# DE-120824.net
KiCad netlist of a schematic drawn in Altium Designer
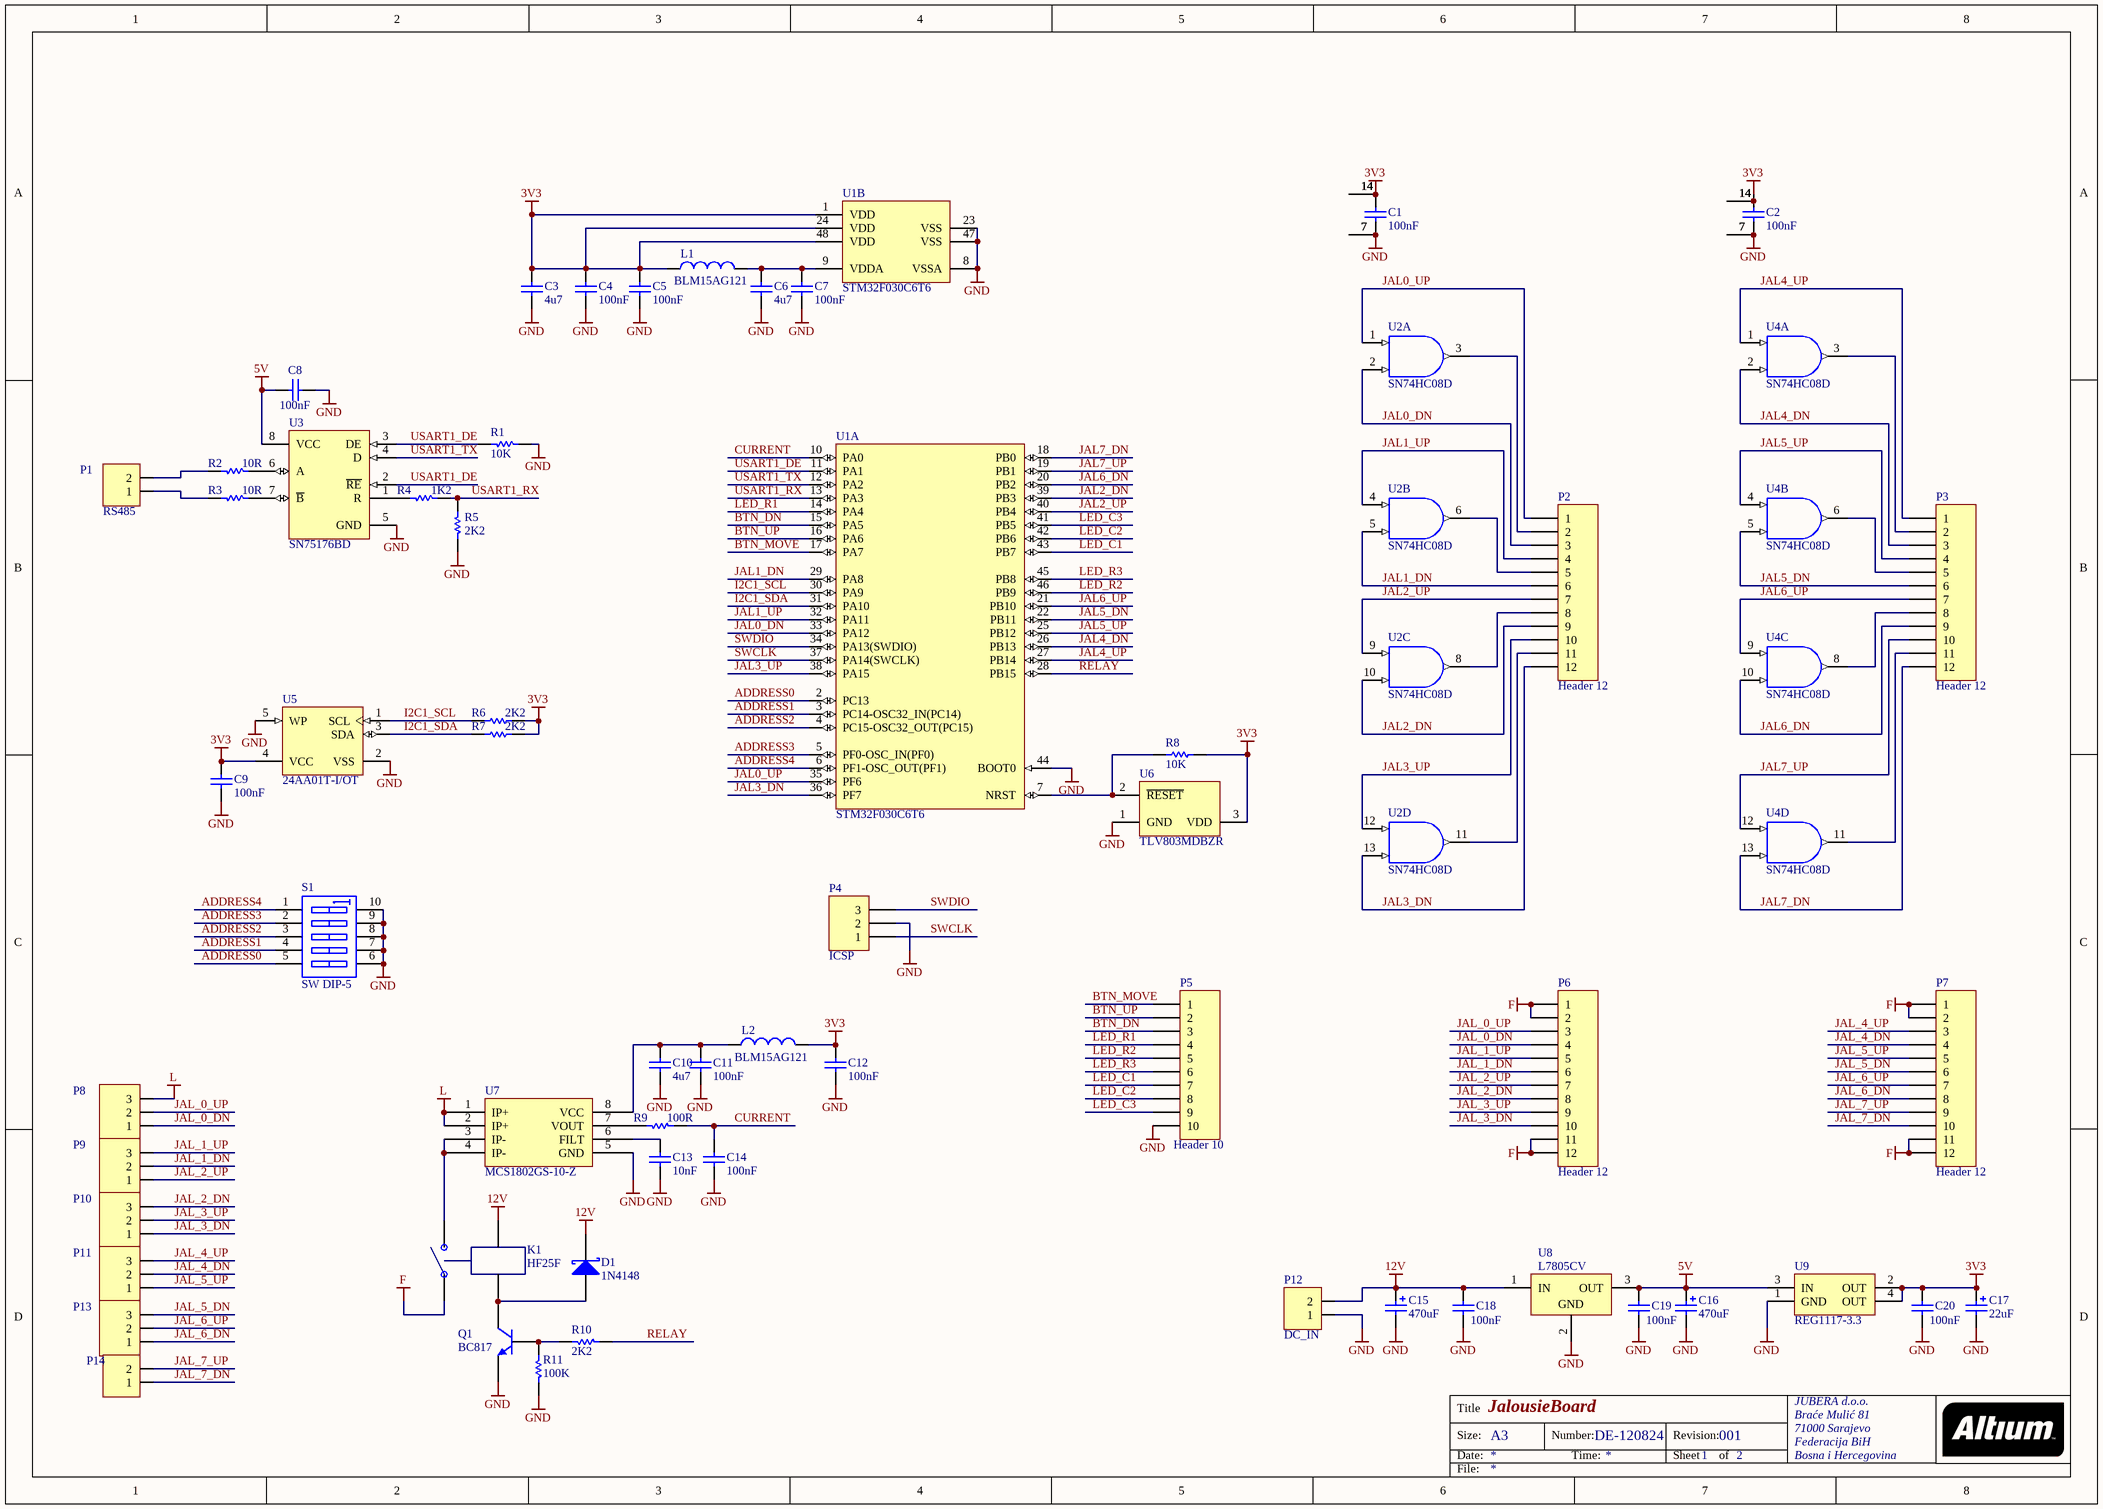
[diagram p0: DE-120824.SchDoc]

(export (version "E")
  (design (tool "Eeschema 10.0.6"))
  (components
    (comp (ref "C1")
      (value "100nF")
      (footprint "0603")
      (description "Ceramic Chip Capacitor - Standard")
      (fields (field (name "Comment") "C0603") (field (name "PUBLISHER") "Altium Limited"))
      (libsource (lib "DE-120824") (part "C0603"))
    )
    (comp (ref "C2")
      (value "100nF")
      (footprint "0603")
      (description "Ceramic Chip Capacitor - Standard")
      (fields (field (name "Comment") "C0603") (field (name "PUBLISHER") "Altium Limited"))
      (libsource (lib "DE-120824") (part "C0603"))
    )
    (comp (ref "C3")
      (value "4u7")
      (footprint "0805")
      (description "Ceramic Chip Capacitor - Standard")
      (fields (field (name "Comment") "C0805") (field (name "PUBLISHER") "Altium Limited"))
      (libsource (lib "DE-120824") (part "C0805"))
    )
    (comp (ref "C4")
      (value "100nF")
      (footprint "0603")
      (description "Ceramic Chip Capacitor - Standard")
      (fields (field (name "Comment") "C0603") (field (name "PUBLISHER") "Altium Limited"))
      (libsource (lib "DE-120824") (part "C0603"))
    )
    (comp (ref "C5")
      (value "100nF")
      (footprint "0603")
      (description "Ceramic Chip Capacitor - Standard")
      (fields (field (name "Comment") "C0603") (field (name "PUBLISHER") "Altium Limited"))
      (libsource (lib "DE-120824") (part "C0603"))
    )
    (comp (ref "C6")
      (value "4u7")
      (footprint "0805")
      (description "Ceramic Chip Capacitor - Standard")
      (fields (field (name "Comment") "C0805") (field (name "PUBLISHER") "Altium Limited"))
      (libsource (lib "DE-120824") (part "C0805"))
    )
    (comp (ref "C7")
      (value "100nF")
      (footprint "0603")
      (description "Ceramic Chip Capacitor - Standard")
      (fields (field (name "Comment") "C0603") (field (name "PUBLISHER") "Altium Limited"))
      (libsource (lib "DE-120824") (part "C0603"))
    )
    (comp (ref "C8")
      (value "100nF")
      (footprint "0603")
      (description "Ceramic Chip Capacitor - Standard")
      (fields (field (name "PUBLISHER") "Altium Limited"))
      (libsource (lib "DE-220817") (part "C0603"))
    )
    (comp (ref "C9")
      (value "100nF")
      (footprint "0603")
      (description "Ceramic Chip Capacitor - Standard")
      (fields (field (name "Comment") "C0603") (field (name "PUBLISHER") "Altium Limited"))
      (libsource (lib "DE-120824") (part "C0603"))
    )
    (comp (ref "C10")
      (value "4u7")
      (footprint "0805")
      (description "Ceramic Chip Capacitor - Standard")
      (fields (field (name "Comment") "C0805") (field (name "PUBLISHER") "Altium Limited"))
      (libsource (lib "DE-120824") (part "C0805"))
    )
    (comp (ref "C11")
      (value "100nF")
      (footprint "0603")
      (description "Ceramic Chip Capacitor - Standard")
      (fields (field (name "Comment") "C0603") (field (name "PUBLISHER") "Altium Limited"))
      (libsource (lib "DE-120824") (part "C0603"))
    )
    (comp (ref "C12")
      (value "100nF")
      (footprint "0603")
      (description "Ceramic Chip Capacitor - Standard")
      (fields (field (name "Comment") "C0603") (field (name "PUBLISHER") "Altium Limited"))
      (libsource (lib "DE-120824") (part "C0603"))
    )
    (comp (ref "C13")
      (value "10nF")
      (footprint "0603")
      (description "Ceramic Chip Capacitor - Standard")
      (fields (field (name "Comment") "C0603") (field (name "PUBLISHER") "Altium Limited"))
      (libsource (lib "DE-120824") (part "C0603"))
    )
    (comp (ref "C14")
      (value "100nF")
      (footprint "0603")
      (description "Ceramic Chip Capacitor - Standard")
      (fields (field (name "Comment") "C0603") (field (name "PUBLISHER") "Altium Limited"))
      (libsource (lib "DE-120824") (part "C0603"))
    )
    (comp (ref "C15")
      (value "470uF")
      (footprint "CAPPR5-10X12.5")
      (description "Aluminum Electrolytic Capacitor, Radial Style with Long Leads: 470uF, 25V")
      (fields (field (name "PUBLISHER") "Altium Limited"))
      (libsource (lib "DE-010824") (part "EKA00DC347E00"))
    )
    (comp (ref "C16")
      (value "470uF")
      (footprint "CAPPR5-10X12.5")
      (description "Aluminum Electrolytic Capacitor, Radial Style with Long Leads: 470uF, 25V")
      (fields (field (name "PUBLISHER") "Altium Limited"))
      (libsource (lib "DE-010824") (part "EKA00DC347E00"))
    )
    (comp (ref "C17")
      (value "22uF")
      (footprint "CAPPR2-5X11")
      (description "Aluminum Electrolytic Capacitor, Radial Style with Long Leads: 47uF, 35V")
      (fields (field (name "PUBLISHER") "Altium Limited"))
      (libsource (lib "DE-010824") (part "EKA00AA247F00"))
    )
    (comp (ref "C18")
      (value "100nF")
      (footprint "0603")
      (description "Ceramic Chip Capacitor - Standard")
      (fields (field (name "PUBLISHER") "Altium Limited"))
      (libsource (lib "DE-220817") (part "C0603"))
    )
    (comp (ref "C19")
      (value "100nF")
      (footprint "0603")
      (description "Ceramic Chip Capacitor - Standard")
      (fields (field (name "PUBLISHER") "Altium Limited"))
      (libsource (lib "DE-220817") (part "C0603"))
    )
    (comp (ref "C20")
      (value "100nF")
      (footprint "0603")
      (description "Ceramic Chip Capacitor - Standard")
      (fields (field (name "PUBLISHER") "Altium Limited"))
      (libsource (lib "DE-220817") (part "C0603"))
    )
    (comp (ref "D1")
      (value "1N4148")
      (footprint "SOD323")
      (description "Schottky Barrier Diode")
      (fields (field (name "PUBLISHER") "Altium Limited"))
      (libsource (lib "DE-120824") (part "1PS76SB10"))
    )
    (comp (ref "K1")
      (value "HF25F")
      (footprint "HF25F")
      (description "PCB relay 250VAC/20A 30VDC/16A")
      (libsource (lib "DE-120824") (part "HF25F"))
    )
    (comp (ref "L1")
      (value "BLM15AG121")
      (footprint "0402-A")
      (description "SMD chip inductor")
      (fields (field (name "PUBLISHER") "Altium Limited"))
      (libsource (lib "DE-120824") (part "Chip inductor"))
    )
    (comp (ref "L2")
      (value "BLM15AG121")
      (footprint "0402-A")
      (description "SMD chip inductor")
      (fields (field (name "PUBLISHER") "Altium Limited"))
      (libsource (lib "DE-120824") (part "Chip inductor"))
    )
    (comp (ref "P1")
      (value "RS485")
      (footprint "TERMINAL BLOK 2")
      (description "Terminal blok konektor 3,5 mm")
      (libsource (lib "DE-120824") (part "TERMINAL BLOK 2"))
    )
    (comp (ref "P2")
      (value "Header 12")
      (footprint "HDR1X12")
      (description "Header, 12-Pin")
      (fields (field (name "PUBLISHER") "Altium Limited"))
      (libsource (lib "Miscellaneous Connectors") (part "Header 12"))
    )
    (comp (ref "P3")
      (value "Header 12")
      (footprint "HDR1X12")
      (description "Header, 12-Pin")
      (fields (field (name "PUBLISHER") "Altium Limited"))
      (libsource (lib "Miscellaneous Connectors") (part "Header 12"))
    )
    (comp (ref "P4")
      (value "ICSP")
      (footprint "HDR1X3")
      (description "Header, 3-Pin")
      (fields (field (name "PUBLISHER") "Altium Limited"))
      (libsource (lib "Miscellaneous Connectors") (part "Header 3"))
    )
    (comp (ref "P5")
      (value "Header 10")
      (footprint "HDR1X10")
      (description "Header, 10-Pin")
      (fields (field (name "PUBLISHER") "Altium Limited"))
      (libsource (lib "Miscellaneous Connectors") (part "Header 10"))
    )
    (comp (ref "P6")
      (value "Header 12")
      (footprint "HDR1X12")
      (description "Header, 12-Pin")
      (fields (field (name "PUBLISHER") "Altium Limited"))
      (libsource (lib "Miscellaneous Connectors") (part "Header 12"))
    )
    (comp (ref "P7")
      (value "Header 12")
      (footprint "HDR1X12")
      (description "Header, 12-Pin")
      (fields (field (name "PUBLISHER") "Altium Limited"))
      (libsource (lib "Miscellaneous Connectors") (part "Header 12"))
    )
    (comp (ref "P8")
      (value "~")
      (footprint "TERMINAL BLOK 3")
      (description "3 pinski terminal blok konektor")
      (libsource (lib "DE-120824") (part "TERMINAL BLOK 3"))
    )
    (comp (ref "P9")
      (value "~")
      (footprint "TERMINAL BLOK 3")
      (description "3 pinski terminal blok konektor")
      (libsource (lib "DE-120824") (part "TERMINAL BLOK 3"))
    )
    (comp (ref "P10")
      (value "~")
      (footprint "TERMINAL BLOK 3")
      (description "3 pinski terminal blok konektor")
      (libsource (lib "DE-120824") (part "TERMINAL BLOK 3"))
    )
    (comp (ref "P11")
      (value "~")
      (footprint "TERMINAL BLOK 3")
      (description "3 pinski terminal blok konektor")
      (libsource (lib "DE-120824") (part "TERMINAL BLOK 3"))
    )
    (comp (ref "P12")
      (value "DC_IN")
      (footprint "TERMINAL BLOK 2")
      (description "Terminal blok konektor 3,5 mm")
      (libsource (lib "DE-010824") (part "TERMINAL BLOK 2"))
    )
    (comp (ref "P13")
      (value "~")
      (footprint "TERMINAL BLOK 3")
      (description "3 pinski terminal blok konektor")
      (libsource (lib "DE-120824") (part "TERMINAL BLOK 3"))
    )
    (comp (ref "P14")
      (value "~")
      (footprint "TERMINAL BLOK 2")
      (description "Terminal blok konektor 3,5 mm")
      (libsource (lib "DE-120824") (part "TERMINAL BLOK 2"))
    )
    (comp (ref "Q1")
      (value "BC817")
      (footprint "SOT23_N")
      (description "NPN General-purpose Transistor")
      (fields (field (name "PUBLISHER") "Altium Limited"))
      (libsource (lib "DE-120824") (part "BC817"))
    )
    (comp (ref "R1")
      (value "10K")
      (footprint "ERA-0603")
      (fields (field (name "PUBLISHER") "Altium Limited"))
      (libsource (lib "DE-220817") (part "ERAV"))
    )
    (comp (ref "R2")
      (value "10R")
      (footprint "ERA-0603")
      (fields (field (name "PUBLISHER") "Altium Limited"))
      (libsource (lib "DE-220817") (part "ERAV"))
    )
    (comp (ref "R3")
      (value "10R")
      (footprint "ERA-0603")
      (fields (field (name "PUBLISHER") "Altium Limited"))
      (libsource (lib "DE-220817") (part "ERAV"))
    )
    (comp (ref "R4")
      (value "1K2")
      (footprint "ERA-0603")
      (fields (field (name "PUBLISHER") "Altium Limited"))
      (libsource (lib "DE-220817") (part "ERAV"))
    )
    (comp (ref "R5")
      (value "2K2")
      (footprint "ERA-0603")
      (fields (field (name "PUBLISHER") "Altium Limited"))
      (libsource (lib "DE-220817") (part "ERAV"))
    )
    (comp (ref "R6")
      (value "2K2")
      (footprint "ERA-0603")
      (fields (field (name "PUBLISHER") "Altium Limited"))
      (libsource (lib "DE-120824") (part "ERA3Y"))
    )
    (comp (ref "R7")
      (value "2K2")
      (footprint "ERA-0603")
      (fields (field (name "PUBLISHER") "Altium Limited"))
      (libsource (lib "DE-120824") (part "ERA3Y"))
    )
    (comp (ref "R8")
      (value "10K")
      (footprint "ERA-0603")
      (fields (field (name "PUBLISHER") "Altium Limited"))
      (libsource (lib "DE-120824") (part "ERA3Y"))
    )
    (comp (ref "R9")
      (value "100R")
      (footprint "ERA-0603")
      (fields (field (name "PUBLISHER") "Altium Limited"))
      (libsource (lib "DE-220817") (part "ERAV"))
    )
    (comp (ref "R10")
      (value "2K2")
      (footprint "ERA-0603")
      (fields (field (name "PUBLISHER") "Altium Limited"))
      (libsource (lib "DE-220817") (part "ERAV"))
    )
    (comp (ref "R11")
      (value "100K")
      (footprint "ERA-0603")
      (fields (field (name "PUBLISHER") "Altium Limited"))
      (libsource (lib "DE-220817") (part "ERAV"))
    )
    (comp (ref "S1")
      (value "SW DIP-5")
      (footprint "N10A")
      (description "DIP Switch, 5 Position, SPST")
      (fields (field (name "PUBLISHER") "Altium Limited"))
      (libsource (lib "Miscellaneous Devices") (part "SW DIP-5"))
    )
    (comp (ref "U1")
      (value "STM32F030C6T6")
      (footprint "STM-LQFP48_N")
      (libsource (lib "STMicroelectronics STM32 F0") (part "STM32F030C6T6"))
    )
    (comp (ref "U2")
      (value "SN74HC08D")
      (footprint "D014_N")
      (description "Quadruple 2-Input Positive-AND Gate")
      (fields (field (name "PUBLISHER") "Altium Limited"))
      (libsource (lib "") (part "SN74HC08D_6"))
    )
    (comp (ref "U3")
      (value "SN75176BD")
      (footprint "D008_N")
      (description "Differential Bus Transceiver")
      (fields (field (name "PUBLISHER") "Altium Limited"))
      (libsource (lib "DE-010824") (part "SN75176BD"))
    )
    (comp (ref "U4")
      (value "SN74HC08D")
      (footprint "D014_N")
      (description "Quadruple 2-Input Positive-AND Gate")
      (fields (field (name "PUBLISHER") "Altium Limited"))
      (libsource (lib "") (part "SN74HC08D_4"))
    )
    (comp (ref "U5")
      (value "24AA01T-I/OT")
      (footprint "SOT-23-OT5_N")
      (description "1Kbit, 400kHz, 1.8V, I2C Serial EEPROM, 5-Pin SOT-23, Industrial Temperature, Tape and Reel")
      (fields (field (name "PUBLISHER") "Altium Limited"))
      (libsource (lib "Microchip Memory I2C Serial EEPROM") (part "24AA01T-I/OT"))
    )
    (comp (ref "U6")
      (value "TLV803MDBZR")
      (footprint "DBZ3_N")
      (fields (field (name "MANUFACTURER") "Texas Instruments"))
      (libsource (lib "TI Power Management Supervisor and Reset IC") (part "TLV803MDBZR"))
    )
    (comp (ref "U7")
      (value "MCS1802GS-10-Z")
      (footprint "SOIC-SN8_N")
      (libsource (lib "DE-120824") (part "ACS71240"))
    )
    (comp (ref "U8")
      (value "L7805CV")
      (footprint "TO220")
      (description "Positive Voltage Regulator, 5V, 3-Pin TO-220")
      (libsource (lib "DE-010824") (part "L7805CV"))
    )
    (comp (ref "U9")
      (value "REG1117-3.3")
      (footprint "ZZ311")
      (description "800mA and 1A Low Dropout Positive Regulator 2.85V, 3.3V, 5V, and Adjustable")
      (fields (field (name "PUBLISHER") "Altium Limited"))
      (libsource (lib "DE-010824") (part "REG1117-3.3"))
    )
  )
  (nets
    (net (code "1") (name "/ADDRESS0") (class "Default")
      (node (ref "S1") (pin "5") (pinfunction "A5_5") (pintype "passive"))
      (node (ref "U1") (pin "2") (pinfunction "PC13_2") (pintype "bidirectional"))
    )
    (net (code "2") (name "/ADDRESS1") (class "Default")
      (node (ref "S1") (pin "4") (pinfunction "A4_4") (pintype "passive"))
      (node (ref "U1") (pin "3") (pinfunction "PC14-OSC32_IN(PC14)_3") (pintype "bidirectional"))
    )
    (net (code "3") (name "/ADDRESS2") (class "Default")
      (node (ref "S1") (pin "3") (pinfunction "A3_3") (pintype "passive"))
      (node (ref "U1") (pin "4") (pinfunction "PC15-OSC32_OUT(PC15)_4") (pintype "bidirectional"))
    )
    (net (code "4") (name "/ADDRESS3") (class "Default")
      (node (ref "S1") (pin "2") (pinfunction "A2_2") (pintype "passive"))
      (node (ref "U1") (pin "5") (pinfunction "PF0-OSC_IN(PF0)_5") (pintype "bidirectional"))
    )
    (net (code "5") (name "/ADDRESS4") (class "Default")
      (node (ref "S1") (pin "1") (pinfunction "A1_1") (pintype "passive"))
      (node (ref "U1") (pin "6") (pinfunction "PF1-OSC_OUT(PF1)_6") (pintype "bidirectional"))
    )
    (net (code "6") (name "/BTN_DN") (class "Default")
      (node (ref "P5") (pin "3") (pinfunction "3_3") (pintype "passive"))
      (node (ref "U1") (pin "15") (pinfunction "PA5_15") (pintype "bidirectional"))
    )
    (net (code "7") (name "/BTN_MOVE") (class "Default")
      (node (ref "P5") (pin "1") (pinfunction "1_1") (pintype "passive"))
      (node (ref "U1") (pin "17") (pinfunction "PA7_17") (pintype "bidirectional"))
    )
    (net (code "8") (name "/BTN_UP") (class "Default")
      (node (ref "P5") (pin "2") (pinfunction "2_2") (pintype "passive"))
      (node (ref "U1") (pin "16") (pinfunction "PA6_16") (pintype "bidirectional"))
    )
    (net (code "9") (name "/CURRENT") (class "Default")
      (node (ref "C14") (pin "2") (pinfunction "2_2") (pintype "passive"))
      (node (ref "R9") (pin "1") (pinfunction "1_1") (pintype "passive"))
      (node (ref "U1") (pin "10") (pinfunction "PA0_10") (pintype "bidirectional"))
    )
    (net (code "10") (name "/I2C1_SCL") (class "Default")
      (node (ref "R6") (pin "1") (pinfunction "1_1") (pintype "passive"))
      (node (ref "U1") (pin "30") (pinfunction "PA9_30") (pintype "bidirectional"))
      (node (ref "U5") (pin "1") (pinfunction "SCL_1") (pintype "input"))
    )
    (net (code "11") (name "/I2C1_SDA") (class "Default")
      (node (ref "R7") (pin "1") (pinfunction "1_1") (pintype "passive"))
      (node (ref "U1") (pin "31") (pinfunction "PA10_31") (pintype "bidirectional"))
      (node (ref "U5") (pin "3") (pinfunction "SDA_3") (pintype "bidirectional"))
    )
    (net (code "12") (name "/JAL0_DN") (class "Default")
      (node (ref "P2") (pin "3") (pinfunction "3_3") (pintype "passive"))
      (node (ref "U1") (pin "33") (pinfunction "PA12_33") (pintype "bidirectional"))
      (node (ref "U2") (pin "2") (pinfunction "B_2") (pintype "input"))
    )
    (net (code "13") (name "/JAL0_UP") (class "Default")
      (node (ref "P2") (pin "1") (pinfunction "1_1") (pintype "passive"))
      (node (ref "U1") (pin "35") (pinfunction "PF6_35") (pintype "bidirectional"))
      (node (ref "U2") (pin "1") (pinfunction "A_1") (pintype "input"))
    )
    (net (code "14") (name "/JAL1_DN") (class "Default")
      (node (ref "P2") (pin "6") (pinfunction "6_6") (pintype "passive"))
      (node (ref "U1") (pin "29") (pinfunction "PA8_29") (pintype "bidirectional"))
      (node (ref "U2") (pin "5") (pinfunction "B_5") (pintype "input"))
    )
    (net (code "15") (name "/JAL1_UP") (class "Default")
      (node (ref "P2") (pin "4") (pinfunction "4_4") (pintype "passive"))
      (node (ref "U1") (pin "32") (pinfunction "PA11_32") (pintype "bidirectional"))
      (node (ref "U2") (pin "4") (pinfunction "A_4") (pintype "input"))
    )
    (net (code "16") (name "/JAL2_DN") (class "Default")
      (node (ref "P2") (pin "9") (pinfunction "9_9") (pintype "passive"))
      (node (ref "U1") (pin "39") (pinfunction "PB3_39") (pintype "bidirectional"))
      (node (ref "U2") (pin "10") (pinfunction "B_10") (pintype "input"))
    )
    (net (code "17") (name "/JAL2_UP") (class "Default")
      (node (ref "P2") (pin "7") (pinfunction "7_7") (pintype "passive"))
      (node (ref "U1") (pin "40") (pinfunction "PB4_40") (pintype "bidirectional"))
      (node (ref "U2") (pin "9") (pinfunction "A_9") (pintype "input"))
    )
    (net (code "18") (name "/JAL3_DN") (class "Default")
      (node (ref "P2") (pin "12") (pinfunction "12_12") (pintype "passive"))
      (node (ref "U1") (pin "36") (pinfunction "PF7_36") (pintype "bidirectional"))
      (node (ref "U2") (pin "13") (pinfunction "B_13") (pintype "input"))
    )
    (net (code "19") (name "/JAL3_UP") (class "Default")
      (node (ref "P2") (pin "10") (pinfunction "10_10") (pintype "passive"))
      (node (ref "U1") (pin "38") (pinfunction "PA15_38") (pintype "bidirectional"))
      (node (ref "U2") (pin "12") (pinfunction "A_12") (pintype "input"))
    )
    (net (code "20") (name "/JAL4_DN") (class "Default")
      (node (ref "P3") (pin "3") (pinfunction "3_3") (pintype "passive"))
      (node (ref "U1") (pin "26") (pinfunction "PB13_26") (pintype "bidirectional"))
      (node (ref "U4") (pin "2") (pinfunction "B_2") (pintype "input"))
    )
    (net (code "21") (name "/JAL4_UP") (class "Default")
      (node (ref "P3") (pin "1") (pinfunction "1_1") (pintype "passive"))
      (node (ref "U1") (pin "27") (pinfunction "PB14_27") (pintype "bidirectional"))
      (node (ref "U4") (pin "1") (pinfunction "A_1") (pintype "input"))
    )
    (net (code "22") (name "/JAL5_DN") (class "Default")
      (node (ref "P3") (pin "6") (pinfunction "6_6") (pintype "passive"))
      (node (ref "U1") (pin "22") (pinfunction "PB11_22") (pintype "bidirectional"))
      (node (ref "U4") (pin "5") (pinfunction "B_5") (pintype "input"))
    )
    (net (code "23") (name "/JAL5_UP") (class "Default")
      (node (ref "P3") (pin "4") (pinfunction "4_4") (pintype "passive"))
      (node (ref "U1") (pin "25") (pinfunction "PB12_25") (pintype "bidirectional"))
      (node (ref "U4") (pin "4") (pinfunction "A_4") (pintype "input"))
    )
    (net (code "24") (name "/JAL6_DN") (class "Default")
      (node (ref "P3") (pin "9") (pinfunction "9_9") (pintype "passive"))
      (node (ref "U1") (pin "20") (pinfunction "PB2_20") (pintype "bidirectional"))
      (node (ref "U4") (pin "10") (pinfunction "B_10") (pintype "input"))
    )
    (net (code "25") (name "/JAL6_UP") (class "Default")
      (node (ref "P3") (pin "7") (pinfunction "7_7") (pintype "passive"))
      (node (ref "U1") (pin "21") (pinfunction "PB10_21") (pintype "bidirectional"))
      (node (ref "U4") (pin "9") (pinfunction "A_9") (pintype "input"))
    )
    (net (code "26") (name "/JAL7_DN") (class "Default")
      (node (ref "P3") (pin "12") (pinfunction "12_12") (pintype "passive"))
      (node (ref "U1") (pin "18") (pinfunction "PB0_18") (pintype "bidirectional"))
      (node (ref "U4") (pin "13") (pinfunction "B_13") (pintype "input"))
    )
    (net (code "27") (name "/JAL7_UP") (class "Default")
      (node (ref "P3") (pin "10") (pinfunction "10_10") (pintype "passive"))
      (node (ref "U1") (pin "19") (pinfunction "PB1_19") (pintype "bidirectional"))
      (node (ref "U4") (pin "12") (pinfunction "A_12") (pintype "input"))
    )
    (net (code "28") (name "/JAL_0_DN") (class "Default")
      (node (ref "P6") (pin "4") (pinfunction "4_4") (pintype "passive"))
      (node (ref "P8") (pin "1") (pinfunction "1_1") (pintype "passive"))
    )
    (net (code "29") (name "/JAL_0_UP") (class "Default")
      (node (ref "P6") (pin "3") (pinfunction "3_3") (pintype "passive"))
      (node (ref "P8") (pin "2") (pinfunction "2_2") (pintype "passive"))
    )
    (net (code "30") (name "/JAL_1_DN") (class "Default")
      (node (ref "P6") (pin "6") (pinfunction "6_6") (pintype "passive"))
      (node (ref "P9") (pin "2") (pinfunction "2_2") (pintype "passive"))
    )
    (net (code "31") (name "/JAL_1_UP") (class "Default")
      (node (ref "P6") (pin "5") (pinfunction "5_5") (pintype "passive"))
      (node (ref "P9") (pin "3") (pinfunction "3_3") (pintype "passive"))
    )
    (net (code "32") (name "/JAL_2_DN") (class "Default")
      (node (ref "P10") (pin "3") (pinfunction "3_3") (pintype "passive"))
      (node (ref "P6") (pin "8") (pinfunction "8_8") (pintype "passive"))
    )
    (net (code "33") (name "/JAL_2_UP") (class "Default")
      (node (ref "P6") (pin "7") (pinfunction "7_7") (pintype "passive"))
      (node (ref "P9") (pin "1") (pinfunction "1_1") (pintype "passive"))
    )
    (net (code "34") (name "/JAL_3_DN") (class "Default")
      (node (ref "P10") (pin "1") (pinfunction "1_1") (pintype "passive"))
      (node (ref "P6") (pin "10") (pinfunction "10_10") (pintype "passive"))
    )
    (net (code "35") (name "/JAL_3_UP") (class "Default")
      (node (ref "P10") (pin "2") (pinfunction "2_2") (pintype "passive"))
      (node (ref "P6") (pin "9") (pinfunction "9_9") (pintype "passive"))
    )
    (net (code "36") (name "/JAL_4_DN") (class "Default")
      (node (ref "P11") (pin "2") (pinfunction "2_2") (pintype "passive"))
      (node (ref "P7") (pin "4") (pinfunction "4_4") (pintype "passive"))
    )
    (net (code "37") (name "/JAL_4_UP") (class "Default")
      (node (ref "P11") (pin "3") (pinfunction "3_3") (pintype "passive"))
      (node (ref "P7") (pin "3") (pinfunction "3_3") (pintype "passive"))
    )
    (net (code "38") (name "/JAL_5_DN") (class "Default")
      (node (ref "P13") (pin "3") (pinfunction "3_3") (pintype "passive"))
      (node (ref "P7") (pin "6") (pinfunction "6_6") (pintype "passive"))
    )
    (net (code "39") (name "/JAL_5_UP") (class "Default")
      (node (ref "P11") (pin "1") (pinfunction "1_1") (pintype "passive"))
      (node (ref "P7") (pin "5") (pinfunction "5_5") (pintype "passive"))
    )
    (net (code "40") (name "/JAL_6_DN") (class "Default")
      (node (ref "P13") (pin "1") (pinfunction "1_1") (pintype "passive"))
      (node (ref "P7") (pin "8") (pinfunction "8_8") (pintype "passive"))
    )
    (net (code "41") (name "/JAL_6_UP") (class "Default")
      (node (ref "P13") (pin "2") (pinfunction "2_2") (pintype "passive"))
      (node (ref "P7") (pin "7") (pinfunction "7_7") (pintype "passive"))
    )
    (net (code "42") (name "/JAL_7_DN") (class "Default")
      (node (ref "P14") (pin "1") (pinfunction "1_1") (pintype "passive"))
      (node (ref "P7") (pin "10") (pinfunction "10_10") (pintype "passive"))
    )
    (net (code "43") (name "/JAL_7_UP") (class "Default")
      (node (ref "P14") (pin "2") (pinfunction "2_2") (pintype "passive"))
      (node (ref "P7") (pin "9") (pinfunction "9_9") (pintype "passive"))
    )
    (net (code "44") (name "/LED_C1") (class "Default")
      (node (ref "P5") (pin "7") (pinfunction "7_7") (pintype "passive"))
      (node (ref "U1") (pin "43") (pinfunction "PB7_43") (pintype "bidirectional"))
    )
    (net (code "45") (name "/LED_C2") (class "Default")
      (node (ref "P5") (pin "8") (pinfunction "8_8") (pintype "passive"))
      (node (ref "U1") (pin "42") (pinfunction "PB6_42") (pintype "bidirectional"))
    )
    (net (code "46") (name "/LED_C3") (class "Default")
      (node (ref "P5") (pin "9") (pinfunction "9_9") (pintype "passive"))
      (node (ref "U1") (pin "41") (pinfunction "PB5_41") (pintype "bidirectional"))
    )
    (net (code "47") (name "/LED_R1") (class "Default")
      (node (ref "P5") (pin "4") (pinfunction "4_4") (pintype "passive"))
      (node (ref "U1") (pin "14") (pinfunction "PA4_14") (pintype "bidirectional"))
    )
    (net (code "48") (name "/LED_R2") (class "Default")
      (node (ref "P5") (pin "5") (pinfunction "5_5") (pintype "passive"))
      (node (ref "U1") (pin "46") (pinfunction "PB9_46") (pintype "bidirectional"))
    )
    (net (code "49") (name "/LED_R3") (class "Default")
      (node (ref "P5") (pin "6") (pinfunction "6_6") (pintype "passive"))
      (node (ref "U1") (pin "45") (pinfunction "PB8_45") (pintype "bidirectional"))
    )
    (net (code "50") (name "/RELAY") (class "Default")
      (node (ref "R10") (pin "2") (pinfunction "2_2") (pintype "passive"))
      (node (ref "U1") (pin "28") (pinfunction "PB15_28") (pintype "bidirectional"))
    )
    (net (code "51") (name "/SWCLK") (class "Default")
      (node (ref "P4") (pin "1") (pinfunction "1_1") (pintype "passive"))
      (node (ref "U1") (pin "37") (pinfunction "PA14(SWCLK)_37") (pintype "bidirectional"))
    )
    (net (code "52") (name "/SWDIO") (class "Default")
      (node (ref "P4") (pin "3") (pinfunction "3_3") (pintype "passive"))
      (node (ref "U1") (pin "34") (pinfunction "PA13(SWDIO)_34") (pintype "bidirectional"))
    )
    (net (code "53") (name "/USART1_DE") (class "Default")
      (node (ref "R1") (pin "2") (pinfunction "2_2") (pintype "passive"))
      (node (ref "U1") (pin "11") (pinfunction "PA1_11") (pintype "bidirectional"))
      (node (ref "U3") (pin "2") (pinfunction "~{RE}_2") (pintype "input"))
      (node (ref "U3") (pin "3") (pinfunction "DE_3") (pintype "input"))
    )
    (net (code "54") (name "/USART1_RX") (class "Default")
      (node (ref "R4") (pin "1") (pinfunction "1_1") (pintype "passive"))
      (node (ref "R5") (pin "1") (pinfunction "1_1") (pintype "passive"))
      (node (ref "U1") (pin "13") (pinfunction "PA3_13") (pintype "bidirectional"))
    )
    (net (code "55") (name "/USART1_TX") (class "Default")
      (node (ref "U1") (pin "12") (pinfunction "PA2_12") (pintype "bidirectional"))
      (node (ref "U3") (pin "4") (pinfunction "D_4") (pintype "input"))
    )
    (net (code "56") (name "3V3") (class "Default")
      (node (ref "C1") (pin "1") (pinfunction "1_1") (pintype "passive"))
      (node (ref "C12") (pin "2") (pinfunction "2_2") (pintype "passive"))
      (node (ref "C17") (pin "1") (pinfunction "1_1") (pintype "passive"))
      (node (ref "C2") (pin "1") (pinfunction "1_1") (pintype "passive"))
      (node (ref "C20") (pin "2") (pinfunction "2_2") (pintype "passive"))
      (node (ref "C3") (pin "2") (pinfunction "2_2") (pintype "passive"))
      (node (ref "C4") (pin "2") (pinfunction "2_2") (pintype "passive"))
      (node (ref "C5") (pin "2") (pinfunction "2_2") (pintype "passive"))
      (node (ref "C9") (pin "2") (pinfunction "2_2") (pintype "passive"))
      (node (ref "L1") (pin "1") (pinfunction "1_1") (pintype "passive"))
      (node (ref "L2") (pin "2") (pinfunction "2_2") (pintype "passive"))
      (node (ref "R6") (pin "2") (pinfunction "2_2") (pintype "passive"))
      (node (ref "R7") (pin "2") (pinfunction "2_2") (pintype "passive"))
      (node (ref "R8") (pin "2") (pinfunction "2_2") (pintype "passive"))
      (node (ref "U1") (pin "1") (pinfunction "VDD_1") (pintype "power_in"))
      (node (ref "U1") (pin "24") (pinfunction "VDD_24") (pintype "power_in"))
      (node (ref "U1") (pin "48") (pinfunction "VDD_48") (pintype "power_in"))
      (node (ref "U2") (pin "14") (pinfunction "3V3_14") (pintype "power_in"))
      (node (ref "U5") (pin "4") (pinfunction "VCC_4") (pintype "power_in"))
      (node (ref "U6") (pin "3") (pinfunction "VDD_3") (pintype "power_in"))
      (node (ref "U9") (pin "2") (pinfunction "OUT_2") (pintype "power_in"))
      (node (ref "U9") (pin "4") (pinfunction "OUT_4") (pintype "power_in"))
    )
    (net (code "57") (name "5V") (class "Default")
      (node (ref "C16") (pin "1") (pinfunction "1_1") (pintype "passive"))
      (node (ref "C19") (pin "2") (pinfunction "2_2") (pintype "passive"))
      (node (ref "C8") (pin "1") (pinfunction "1_1") (pintype "passive"))
      (node (ref "U3") (pin "8") (pinfunction "VCC_8") (pintype "power_in"))
      (node (ref "U8") (pin "3") (pinfunction "OUT_3") (pintype "power_in"))
      (node (ref "U9") (pin "3") (pinfunction "IN_3") (pintype "power_in"))
    )
    (net (code "58") (name "12V") (class "Default")
      (node (ref "C15") (pin "1") (pinfunction "1_1") (pintype "passive"))
      (node (ref "C18") (pin "2") (pinfunction "2_2") (pintype "passive"))
      (node (ref "D1") (pin "1") (pinfunction "K_1") (pintype "passive"))
      (node (ref "K1") (pin "2") (pinfunction "2_2") (pintype "passive"))
      (node (ref "P12") (pin "2") (pinfunction "2_2") (pintype "passive"))
      (node (ref "U8") (pin "1") (pinfunction "IN_1") (pintype "power_in"))
    )
    (net (code "59") (name "F") (class "Default")
      (node (ref "K1") (pin "3") (pinfunction "3_3") (pintype "passive"))
      (node (ref "P6") (pin "1") (pinfunction "1_1") (pintype "passive"))
      (node (ref "P6") (pin "11") (pinfunction "11_11") (pintype "passive"))
      (node (ref "P6") (pin "12") (pinfunction "12_12") (pintype "passive"))
      (node (ref "P6") (pin "2") (pinfunction "2_2") (pintype "passive"))
      (node (ref "P7") (pin "1") (pinfunction "1_1") (pintype "passive"))
      (node (ref "P7") (pin "11") (pinfunction "11_11") (pintype "passive"))
      (node (ref "P7") (pin "12") (pinfunction "12_12") (pintype "passive"))
      (node (ref "P7") (pin "2") (pinfunction "2_2") (pintype "passive"))
    )
    (net (code "60") (name "GND") (class "Default")
      (node (ref "C1") (pin "2") (pinfunction "2_2") (pintype "passive"))
      (node (ref "C10") (pin "1") (pinfunction "1_1") (pintype "passive"))
      (node (ref "C11") (pin "1") (pinfunction "1_1") (pintype "passive"))
      (node (ref "C12") (pin "1") (pinfunction "1_1") (pintype "passive"))
      (node (ref "C13") (pin "1") (pinfunction "1_1") (pintype "passive"))
      (node (ref "C14") (pin "1") (pinfunction "1_1") (pintype "passive"))
      (node (ref "C15") (pin "2") (pinfunction "2_2") (pintype "passive"))
      (node (ref "C16") (pin "2") (pinfunction "2_2") (pintype "passive"))
      (node (ref "C17") (pin "2") (pinfunction "2_2") (pintype "passive"))
      (node (ref "C18") (pin "1") (pinfunction "1_1") (pintype "passive"))
      (node (ref "C19") (pin "1") (pinfunction "1_1") (pintype "passive"))
      (node (ref "C2") (pin "2") (pinfunction "2_2") (pintype "passive"))
      (node (ref "C20") (pin "1") (pinfunction "1_1") (pintype "passive"))
      (node (ref "C3") (pin "1") (pinfunction "1_1") (pintype "passive"))
      (node (ref "C4") (pin "1") (pinfunction "1_1") (pintype "passive"))
      (node (ref "C5") (pin "1") (pinfunction "1_1") (pintype "passive"))
      (node (ref "C6") (pin "1") (pinfunction "1_1") (pintype "passive"))
      (node (ref "C7") (pin "1") (pinfunction "1_1") (pintype "passive"))
      (node (ref "C8") (pin "2") (pinfunction "2_2") (pintype "passive"))
      (node (ref "C9") (pin "1") (pinfunction "1_1") (pintype "passive"))
      (node (ref "P12") (pin "1") (pinfunction "1_1") (pintype "passive"))
      (node (ref "P4") (pin "2") (pinfunction "2_2") (pintype "passive"))
      (node (ref "P5") (pin "10") (pinfunction "10_10") (pintype "passive"))
      (node (ref "Q1") (pin "2") (pinfunction "E_2") (pintype "passive"))
      (node (ref "R1") (pin "1") (pinfunction "1_1") (pintype "passive"))
      (node (ref "R11") (pin "1") (pinfunction "1_1") (pintype "passive"))
      (node (ref "R5") (pin "2") (pinfunction "2_2") (pintype "passive"))
      (node (ref "S1") (pin "10") (pinfunction "B1_10") (pintype "passive"))
      (node (ref "S1") (pin "6") (pinfunction "B5_6") (pintype "passive"))
      (node (ref "S1") (pin "7") (pinfunction "B4_7") (pintype "passive"))
      (node (ref "S1") (pin "8") (pinfunction "B3_8") (pintype "passive"))
      (node (ref "S1") (pin "9") (pinfunction "B2_9") (pintype "passive"))
      (node (ref "U1") (pin "23") (pinfunction "VSS_23") (pintype "power_in"))
      (node (ref "U1") (pin "44") (pinfunction "BOOT0_44") (pintype "input"))
      (node (ref "U1") (pin "47") (pinfunction "VSS_47") (pintype "power_in"))
      (node (ref "U1") (pin "8") (pinfunction "VSSA_8") (pintype "power_in"))
      (node (ref "U2") (pin "7") (pinfunction "GND_7") (pintype "power_in"))
      (node (ref "U3") (pin "5") (pinfunction "GND_5") (pintype "power_in"))
      (node (ref "U4") (pin "7") (pinfunction "GND_7") (pintype "power_in"))
      (node (ref "U5") (pin "2") (pinfunction "VSS_2") (pintype "power_in"))
      (node (ref "U5") (pin "5") (pinfunction "WP_5") (pintype "input"))
      (node (ref "U6") (pin "1") (pinfunction "GND_1") (pintype "power_in"))
      (node (ref "U7") (pin "5") (pinfunction "GND_5") (pintype "passive"))
      (node (ref "U8") (pin "2") (pinfunction "GND_2") (pintype "power_in"))
      (node (ref "U9") (pin "1") (pinfunction "GND_1") (pintype "power_in"))
    )
    (net (code "61") (name "L") (class "Default")
      (node (ref "P8") (pin "3") (pinfunction "3_3") (pintype "passive"))
      (node (ref "U7") (pin "1") (pinfunction "IP+_1") (pintype "passive"))
      (node (ref "U7") (pin "2") (pinfunction "IP+_2") (pintype "passive"))
    )
    (net (code "62") (name "Net-(D1-A)") (class "Default")
      (node (ref "D1") (pin "2") (pinfunction "A_2") (pintype "passive"))
      (node (ref "K1") (pin "1") (pinfunction "1_1") (pintype "passive"))
      (node (ref "Q1") (pin "3") (pinfunction "C_3") (pintype "passive"))
    )
    (net (code "63") (name "Net-(K1-Pad4)") (class "Default")
      (node (ref "K1") (pin "4") (pinfunction "4_4") (pintype "passive"))
      (node (ref "U7") (pin "3") (pinfunction "IP-_3") (pintype "passive"))
      (node (ref "U7") (pin "4") (pinfunction "IP-_4") (pintype "passive"))
    )
    (net (code "64") (name "Net-(P1-Pad1)") (class "Default")
      (node (ref "P1") (pin "1") (pinfunction "1_1") (pintype "passive"))
      (node (ref "R3") (pin "1") (pinfunction "1_1") (pintype "passive"))
    )
    (net (code "65") (name "Net-(P1-Pad2)") (class "Default")
      (node (ref "P1") (pin "2") (pinfunction "2_2") (pintype "passive"))
      (node (ref "R2") (pin "1") (pinfunction "1_1") (pintype "passive"))
    )
    (net (code "66") (name "Net-(Q1-B)") (class "Default")
      (node (ref "Q1") (pin "1") (pinfunction "B_1") (pintype "passive"))
      (node (ref "R10") (pin "1") (pinfunction "1_1") (pintype "passive"))
      (node (ref "R11") (pin "2") (pinfunction "2_2") (pintype "passive"))
    )
    (net (code "67") (name "Net-(U1A-NRST)") (class "Default")
      (node (ref "R8") (pin "1") (pinfunction "1_1") (pintype "passive"))
      (node (ref "U1") (pin "7") (pinfunction "NRST_7") (pintype "bidirectional"))
      (node (ref "U6") (pin "2") (pinfunction "~{RESET}_2") (pintype "open_collector"))
    )
    (net (code "68") (name "Net-(U1B-VDDA)") (class "Default")
      (node (ref "C6") (pin "2") (pinfunction "2_2") (pintype "passive"))
      (node (ref "C7") (pin "2") (pinfunction "2_2") (pintype "passive"))
      (node (ref "L1") (pin "2") (pinfunction "2_2") (pintype "passive"))
      (node (ref "U1") (pin "9") (pinfunction "VDDA_9") (pintype "power_in"))
    )
    (net (code "69") (name "Net-(U2A-Y)") (class "Default")
      (node (ref "P2") (pin "2") (pinfunction "2_2") (pintype "passive"))
      (node (ref "U2") (pin "3") (pinfunction "Y_3") (pintype "output"))
    )
    (net (code "70") (name "Net-(U2B-Y)") (class "Default")
      (node (ref "P2") (pin "5") (pinfunction "5_5") (pintype "passive"))
      (node (ref "U2") (pin "6") (pinfunction "Y_6") (pintype "output"))
    )
    (net (code "71") (name "Net-(U2C-Y)") (class "Default")
      (node (ref "P2") (pin "8") (pinfunction "8_8") (pintype "passive"))
      (node (ref "U2") (pin "8") (pinfunction "Y_8") (pintype "output"))
    )
    (net (code "72") (name "Net-(U2D-Y)") (class "Default")
      (node (ref "P2") (pin "11") (pinfunction "11_11") (pintype "passive"))
      (node (ref "U2") (pin "11") (pinfunction "Y_11") (pintype "output"))
    )
    (net (code "73") (name "Net-(U3-A)") (class "Default")
      (node (ref "R2") (pin "2") (pinfunction "2_2") (pintype "passive"))
      (node (ref "U3") (pin "6") (pinfunction "A_6") (pintype "bidirectional"))
    )
    (net (code "74") (name "Net-(U3-R)") (class "Default")
      (node (ref "R4") (pin "2") (pinfunction "2_2") (pintype "passive"))
      (node (ref "U3") (pin "1") (pinfunction "R_1") (pintype "tri_state"))
    )
    (net (code "75") (name "Net-(U3-~{B})") (class "Default")
      (node (ref "R3") (pin "2") (pinfunction "2_2") (pintype "passive"))
      (node (ref "U3") (pin "7") (pinfunction "~{B}_7") (pintype "bidirectional"))
    )
    (net (code "76") (name "Net-(U4A-3V3)") (class "Default")
      (node (ref "U4") (pin "14") (pinfunction "3V3_14") (pintype "power_in"))
    )
    (net (code "77") (name "Net-(U4A-Y)") (class "Default")
      (node (ref "P3") (pin "2") (pinfunction "2_2") (pintype "passive"))
      (node (ref "U4") (pin "3") (pinfunction "Y_3") (pintype "output"))
    )
    (net (code "78") (name "Net-(U4B-Y)") (class "Default")
      (node (ref "P3") (pin "5") (pinfunction "5_5") (pintype "passive"))
      (node (ref "U4") (pin "6") (pinfunction "Y_6") (pintype "output"))
    )
    (net (code "79") (name "Net-(U4C-Y)") (class "Default")
      (node (ref "P3") (pin "8") (pinfunction "8_8") (pintype "passive"))
      (node (ref "U4") (pin "8") (pinfunction "Y_8") (pintype "output"))
    )
    (net (code "80") (name "Net-(U4D-Y)") (class "Default")
      (node (ref "P3") (pin "11") (pinfunction "11_11") (pintype "passive"))
      (node (ref "U4") (pin "11") (pinfunction "Y_11") (pintype "output"))
    )
    (net (code "81") (name "Net-(U7-FILT)") (class "Default")
      (node (ref "C13") (pin "2") (pinfunction "2_2") (pintype "passive"))
      (node (ref "U7") (pin "6") (pinfunction "FILT_6") (pintype "passive"))
    )
    (net (code "82") (name "Net-(U7-VCC)") (class "Default")
      (node (ref "C10") (pin "2") (pinfunction "2_2") (pintype "passive"))
      (node (ref "C11") (pin "2") (pinfunction "2_2") (pintype "passive"))
      (node (ref "L2") (pin "1") (pinfunction "1_1") (pintype "passive"))
      (node (ref "U7") (pin "8") (pinfunction "VCC_8") (pintype "passive"))
    )
    (net (code "83") (name "Net-(U7-VOUT)") (class "Default")
      (node (ref "R9") (pin "2") (pinfunction "2_2") (pintype "passive"))
      (node (ref "U7") (pin "7") (pinfunction "VOUT_7") (pintype "passive"))
    )
  )
)
